# nintendac.net
KiCad netlist of a schematic drawn in EAGLE
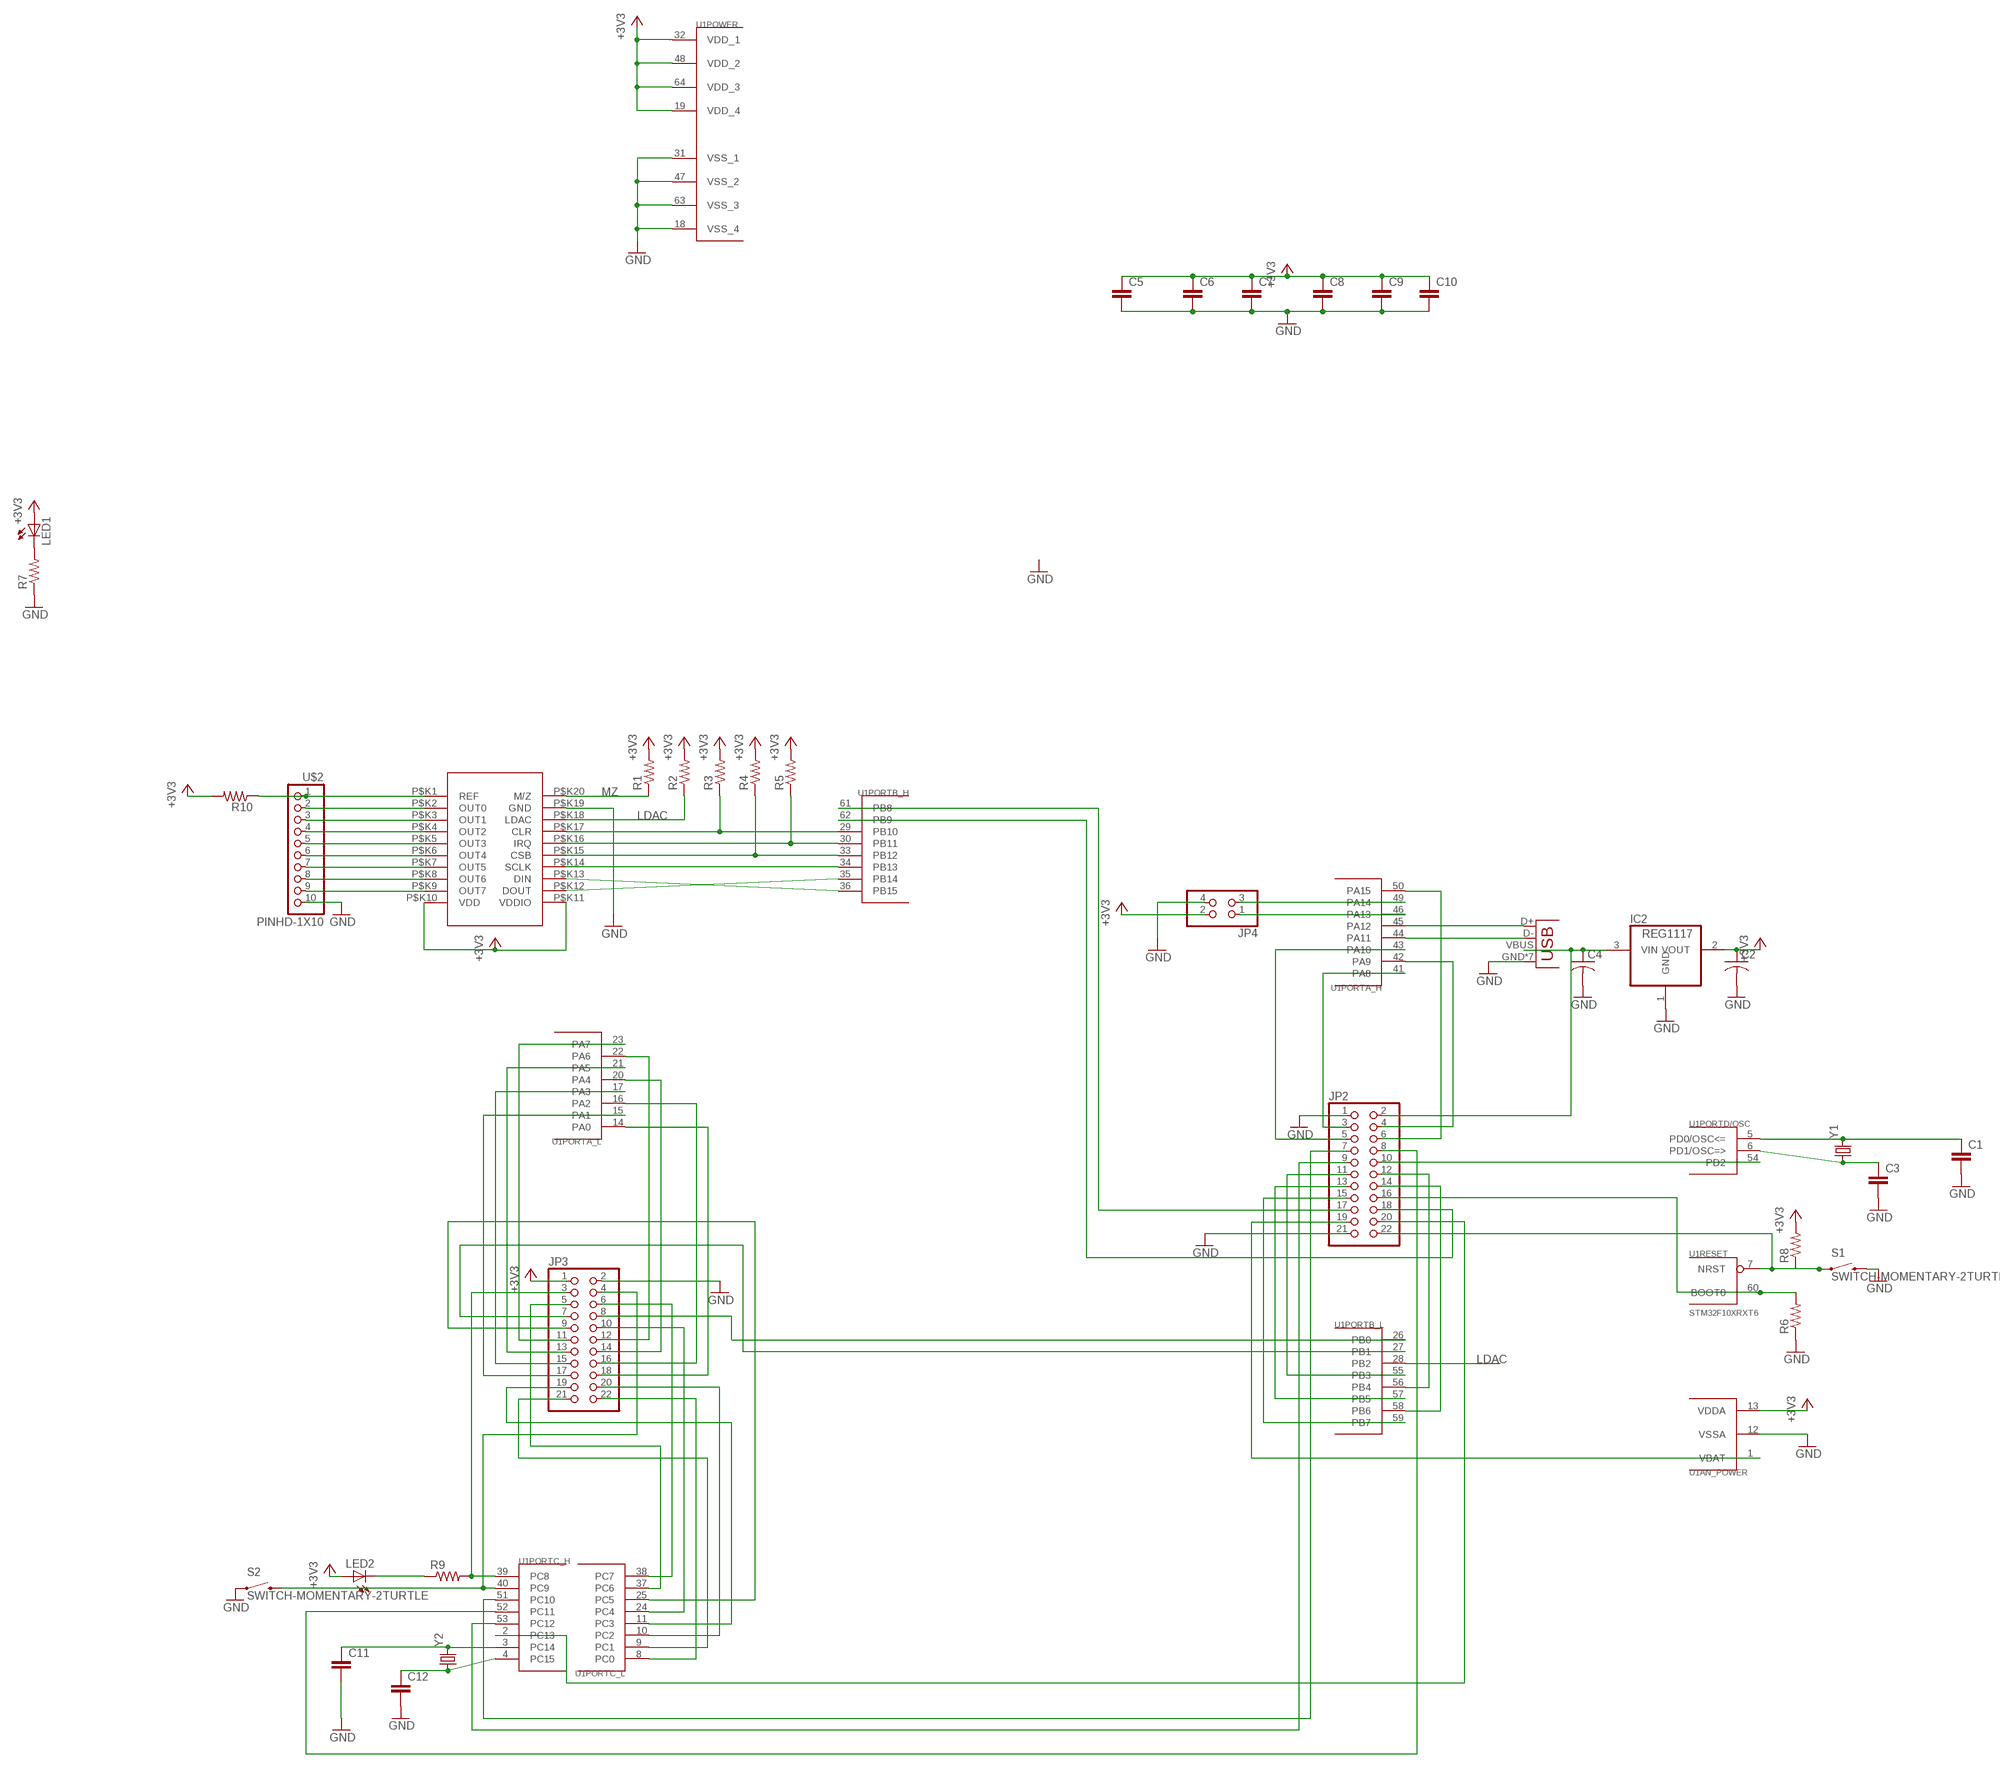
[diagram p0: schematic, sheet 1]

(export (version "E")
  (design (tool "Eeschema 10.0.6"))
  (components
    (comp (ref "C1")
      (value "CAP0805")
      (footprint "eagle-import:0805")
      (libsource (lib "eagle-import") (part "CAP0805"))
    )
    (comp (ref "C2")
      (value "C-USC1210")
      (footprint "eagle-import:C1210")
      (libsource (lib "eagle-import") (part "C-USC1210"))
    )
    (comp (ref "C3")
      (value "CAP0805")
      (footprint "eagle-import:0805")
      (libsource (lib "eagle-import") (part "CAP0805"))
    )
    (comp (ref "C4")
      (value "C-USC1210")
      (footprint "eagle-import:C1210")
      (libsource (lib "eagle-import") (part "C-USC1210"))
    )
    (comp (ref "C5")
      (value "CAP0805")
      (footprint "eagle-import:0805")
      (libsource (lib "eagle-import") (part "CAP0805"))
    )
    (comp (ref "C6")
      (value "CAP0805")
      (footprint "eagle-import:0805")
      (libsource (lib "eagle-import") (part "CAP0805"))
    )
    (comp (ref "C7")
      (value "CAP0805")
      (footprint "eagle-import:0805")
      (libsource (lib "eagle-import") (part "CAP0805"))
    )
    (comp (ref "C8")
      (value "CAP0805")
      (footprint "eagle-import:0805")
      (libsource (lib "eagle-import") (part "CAP0805"))
    )
    (comp (ref "C9")
      (value "CAP0805")
      (footprint "eagle-import:0805")
      (libsource (lib "eagle-import") (part "CAP0805"))
    )
    (comp (ref "C10")
      (value "CAP0805")
      (footprint "eagle-import:0805")
      (libsource (lib "eagle-import") (part "CAP0805"))
    )
    (comp (ref "C11")
      (value "CAP0805")
      (footprint "eagle-import:0805")
      (libsource (lib "eagle-import") (part "CAP0805"))
    )
    (comp (ref "C12")
      (value "CAP0805")
      (footprint "eagle-import:0805")
      (libsource (lib "eagle-import") (part "CAP0805"))
    )
    (comp (ref "IC2")
      (value "REG1117")
      (footprint "eagle-import:SOT223")
      (libsource (lib "eagle-import") (part "REG1117"))
    )
    (comp (ref "JP2")
      (value "PINHD-2X11")
      (footprint "eagle-import:2X11")
      (libsource (lib "eagle-import") (part "PINHD-2X11"))
    )
    (comp (ref "JP3")
      (value "PINHD-2X11")
      (footprint "eagle-import:2X11")
      (libsource (lib "eagle-import") (part "PINHD-2X11"))
    )
    (comp (ref "JP4")
      (value "PINHD-2X2")
      (footprint "eagle-import:2X02")
      (libsource (lib "eagle-import") (part "PINHD-2X2"))
    )
    (comp (ref "LED1")
      (value "LEDCHIP-LED0805")
      (footprint "eagle-import:CHIP-LED0805")
      (libsource (lib "eagle-import") (part "LEDCHIP-LED0805"))
    )
    (comp (ref "LED2")
      (value "LEDCHIP-LED0805")
      (footprint "eagle-import:CHIP-LED0805")
      (libsource (lib "eagle-import") (part "LEDCHIP-LED0805"))
    )
    (comp (ref "R1")
      (value "RESISTOR0805-RES")
      (footprint "eagle-import:0805")
      (libsource (lib "eagle-import") (part "RESISTOR0805-RES"))
    )
    (comp (ref "R2")
      (value "RESISTOR0805-RES")
      (footprint "eagle-import:0805")
      (libsource (lib "eagle-import") (part "RESISTOR0805-RES"))
    )
    (comp (ref "R3")
      (value "RESISTOR0805-RES")
      (footprint "eagle-import:0805")
      (libsource (lib "eagle-import") (part "RESISTOR0805-RES"))
    )
    (comp (ref "R4")
      (value "RESISTOR0805-RES")
      (footprint "eagle-import:0805")
      (libsource (lib "eagle-import") (part "RESISTOR0805-RES"))
    )
    (comp (ref "R5")
      (value "RESISTOR0805-RES")
      (footprint "eagle-import:0805")
      (libsource (lib "eagle-import") (part "RESISTOR0805-RES"))
    )
    (comp (ref "R6")
      (value "RESISTOR0805-RES")
      (footprint "eagle-import:0805")
      (libsource (lib "eagle-import") (part "RESISTOR0805-RES"))
    )
    (comp (ref "R7")
      (value "RESISTOR0805-RES")
      (footprint "eagle-import:0805")
      (libsource (lib "eagle-import") (part "RESISTOR0805-RES"))
    )
    (comp (ref "R8")
      (value "RESISTOR0805-RES")
      (footprint "eagle-import:0805")
      (libsource (lib "eagle-import") (part "RESISTOR0805-RES"))
    )
    (comp (ref "R9")
      (value "RESISTOR0805-RES")
      (footprint "eagle-import:0805")
      (libsource (lib "eagle-import") (part "RESISTOR0805-RES"))
    )
    (comp (ref "R10")
      (value "RESISTOR0805-RES")
      (footprint "eagle-import:0805")
      (libsource (lib "eagle-import") (part "RESISTOR0805-RES"))
    )
    (comp (ref "S1")
      (value "SWITCH-MOMENTARY-2TURTLE")
      (footprint "eagle-import:KMR2")
      (libsource (lib "eagle-import") (part "SWITCH-MOMENTARY-2TURTLE"))
    )
    (comp (ref "S2")
      (value "SWITCH-MOMENTARY-2TURTLE")
      (footprint "eagle-import:KMR2")
      (libsource (lib "eagle-import") (part "SWITCH-MOMENTARY-2TURTLE"))
    )
    (comp (ref "U$1")
      (value "MAX572X")
      (footprint "eagle-import:TSSOP20")
      (libsource (lib "eagle-import") (part "MAX572X"))
    )
    (comp (ref "U$2")
      (value "PINHD-1X10")
      (footprint "eagle-import:1X10-BIG")
      (libsource (lib "eagle-import") (part "PINHD-1X10"))
    )
    (comp (ref "U1")
      (value "STM32F10XRXT6")
      (footprint "eagle-import:TQFP64")
      (libsource (lib "eagle-import") (part "STM32F10XRXT6"))
    )
    (comp (ref "X1")
      (value "USB-MICROB")
      (footprint "eagle-import:USB-MICROB")
      (libsource (lib "eagle-import") (part "USB-MICROB"))
    )
    (comp (ref "Y1")
      (value "CRYSTALHC49US")
      (footprint "eagle-import:HC49US")
      (libsource (lib "eagle-import") (part "CRYSTALHC49US"))
    )
    (comp (ref "Y2")
      (value "CRYSTALTC26H_EZ")
      (footprint "eagle-import:TC26HEZ")
      (libsource (lib "eagle-import") (part "CRYSTALTC26H_EZ"))
    )
  )
  (nets
    (net (code "1") (name "+3V3") (class "Default")
      (node (ref "C10") (pin "1") (pinfunction "1_1") (pintype "passive"))
      (node (ref "C2") (pin "1") (pinfunction "1_1") (pintype "passive"))
      (node (ref "C5") (pin "1") (pinfunction "1_1") (pintype "passive"))
      (node (ref "C6") (pin "1") (pinfunction "1_1") (pintype "passive"))
      (node (ref "C7") (pin "1") (pinfunction "1_1") (pintype "passive"))
      (node (ref "C8") (pin "1") (pinfunction "1_1") (pintype "passive"))
      (node (ref "C9") (pin "1") (pinfunction "1_1") (pintype "passive"))
      (node (ref "IC2") (pin "2") (pinfunction "VOUT_2") (pintype "output"))
      (node (ref "JP3") (pin "1") (pinfunction "1_1") (pintype "passive"))
      (node (ref "JP4") (pin "2") (pinfunction "2_2") (pintype "passive"))
      (node (ref "LED1") (pin "A") (pinfunction "A_A") (pintype "passive"))
      (node (ref "LED2") (pin "A") (pinfunction "A_A") (pintype "passive"))
      (node (ref "R1") (pin "2") (pinfunction "2_2") (pintype "passive"))
      (node (ref "R10") (pin "2") (pinfunction "2_2") (pintype "passive"))
      (node (ref "R2") (pin "2") (pinfunction "2_2") (pintype "passive"))
      (node (ref "R3") (pin "2") (pinfunction "2_2") (pintype "passive"))
      (node (ref "R4") (pin "2") (pinfunction "2_2") (pintype "passive"))
      (node (ref "R5") (pin "2") (pinfunction "2_2") (pintype "passive"))
      (node (ref "R8") (pin "2") (pinfunction "2_2") (pintype "passive"))
      (node (ref "U$1") (pin "P$K10") (pinfunction "VDD_P$K10") (pintype "bidirectional"))
      (node (ref "U$1") (pin "P$K11") (pinfunction "VDDIO_P$K11") (pintype "bidirectional"))
      (node (ref "U1") (pin "13") (pinfunction "VDDA_13") (pintype "power_in"))
      (node (ref "U1") (pin "19") (pinfunction "VDD_4_19") (pintype "power_in"))
      (node (ref "U1") (pin "32") (pinfunction "VDD_1_32") (pintype "power_in"))
      (node (ref "U1") (pin "48") (pinfunction "VDD_2_48") (pintype "power_in"))
      (node (ref "U1") (pin "64") (pinfunction "VDD_3_64") (pintype "power_in"))
    )
    (net (code "2") (name "/LDAC") (class "Default")
      (node (ref "R2") (pin "1") (pinfunction "1_1") (pintype "passive"))
      (node (ref "U$1") (pin "P$K18") (pinfunction "LDAC_P$K18") (pintype "bidirectional"))
      (node (ref "U1") (pin "28") (pinfunction "PB2_28") (pintype "bidirectional"))
    )
    (net (code "3") (name "/MZ") (class "Default")
      (node (ref "R1") (pin "1") (pinfunction "1_1") (pintype "passive"))
      (node (ref "U$1") (pin "P$K20") (pinfunction "M/Z_P$K20") (pintype "bidirectional"))
    )
    (net (code "4") (name "GND") (class "Default")
      (node (ref "C1") (pin "2") (pinfunction "2_2") (pintype "passive"))
      (node (ref "C10") (pin "2") (pinfunction "2_2") (pintype "passive"))
      (node (ref "C11") (pin "2") (pinfunction "2_2") (pintype "passive"))
      (node (ref "C12") (pin "2") (pinfunction "2_2") (pintype "passive"))
      (node (ref "C2") (pin "2") (pinfunction "2_2") (pintype "passive"))
      (node (ref "C3") (pin "2") (pinfunction "2_2") (pintype "passive"))
      (node (ref "C4") (pin "2") (pinfunction "2_2") (pintype "passive"))
      (node (ref "C5") (pin "2") (pinfunction "2_2") (pintype "passive"))
      (node (ref "C6") (pin "2") (pinfunction "2_2") (pintype "passive"))
      (node (ref "C7") (pin "2") (pinfunction "2_2") (pintype "passive"))
      (node (ref "C8") (pin "2") (pinfunction "2_2") (pintype "passive"))
      (node (ref "C9") (pin "2") (pinfunction "2_2") (pintype "passive"))
      (node (ref "IC2") (pin "1") (pinfunction "GND_1") (pintype "power_in"))
      (node (ref "JP2") (pin "1") (pinfunction "1_1") (pintype "passive"))
      (node (ref "JP2") (pin "21") (pinfunction "21_21") (pintype "passive"))
      (node (ref "JP3") (pin "2") (pinfunction "2_2") (pintype "passive"))
      (node (ref "JP4") (pin "4") (pinfunction "4_4") (pintype "passive"))
      (node (ref "R6") (pin "1") (pinfunction "1_1") (pintype "passive"))
      (node (ref "R7") (pin "1") (pinfunction "1_1") (pintype "passive"))
      (node (ref "S1") (pin "3") (pinfunction "2_3") (pintype "passive"))
      (node (ref "S2") (pin "1") (pinfunction "1_1") (pintype "passive"))
      (node (ref "U$1") (pin "P$K19") (pinfunction "GND_P$K19") (pintype "bidirectional"))
      (node (ref "U$2") (pin "10") (pinfunction "10_10") (pintype "passive"))
      (node (ref "U1") (pin "12") (pinfunction "VSSA_12") (pintype "power_in"))
      (node (ref "U1") (pin "18") (pinfunction "VSS_4_18") (pintype "power_in"))
      (node (ref "U1") (pin "31") (pinfunction "VSS_1_31") (pintype "power_in"))
      (node (ref "U1") (pin "47") (pinfunction "VSS_2_47") (pintype "power_in"))
      (node (ref "U1") (pin "63") (pinfunction "VSS_3_63") (pintype "power_in"))
      (node (ref "X1") (pin "GND") (pinfunction "GND_GND") (pintype "bidirectional"))
      (node (ref "X1") (pin "P1") (pinfunction "GND_P1") (pintype "bidirectional"))
      (node (ref "X1") (pin "P2") (pinfunction "GND_P2") (pintype "bidirectional"))
      (node (ref "X1") (pin "P3") (pinfunction "GND_P3") (pintype "bidirectional"))
      (node (ref "X1") (pin "P4") (pinfunction "GND_P4") (pintype "bidirectional"))
      (node (ref "X1") (pin "P5") (pinfunction "GND_P5") (pintype "bidirectional"))
      (node (ref "X1") (pin "P6") (pinfunction "GND_P6") (pintype "bidirectional"))
    )
    (net (code "5") (name "Net-(IC2-VIN)") (class "Default")
      (node (ref "C4") (pin "1") (pinfunction "1_1") (pintype "passive"))
      (node (ref "IC2") (pin "3") (pinfunction "VIN_3") (pintype "input"))
      (node (ref "JP2") (pin "2") (pinfunction "2_2") (pintype "passive"))
      (node (ref "X1") (pin "VBUS") (pinfunction "VBUS_VBUS") (pintype "bidirectional"))
    )
    (net (code "6") (name "Net-(LED1-PadC)") (class "Default")
      (node (ref "LED1") (pin "C") (pinfunction "C_C") (pintype "passive"))
      (node (ref "R7") (pin "2") (pinfunction "2_2") (pintype "passive"))
    )
    (net (code "7") (name "Net-(LED2-PadC)") (class "Default")
      (node (ref "LED2") (pin "C") (pinfunction "C_C") (pintype "passive"))
      (node (ref "R9") (pin "1") (pinfunction "1_1") (pintype "passive"))
    )
    (net (code "8") (name "Net-(S2-2)") (class "Default")
      (node (ref "JP3") (pin "4") (pinfunction "4_4") (pintype "passive"))
      (node (ref "S2") (pin "3") (pinfunction "2_3") (pintype "passive"))
      (node (ref "U1") (pin "40") (pinfunction "PC9_40") (pintype "bidirectional"))
    )
    (net (code "9") (name "Net-(U$1-CLR)") (class "Default")
      (node (ref "R3") (pin "1") (pinfunction "1_1") (pintype "passive"))
      (node (ref "U$1") (pin "P$K17") (pinfunction "CLR_P$K17") (pintype "bidirectional"))
      (node (ref "U1") (pin "29") (pinfunction "PB10_29") (pintype "bidirectional"))
    )
    (net (code "10") (name "Net-(U$1-CSB)") (class "Default")
      (node (ref "R4") (pin "1") (pinfunction "1_1") (pintype "passive"))
      (node (ref "U$1") (pin "P$K15") (pinfunction "CSB_P$K15") (pintype "bidirectional"))
      (node (ref "U1") (pin "33") (pinfunction "PB12_33") (pintype "bidirectional"))
    )
    (net (code "11") (name "Net-(U$1-DIN)") (class "Default")
      (node (ref "U$1") (pin "P$K13") (pinfunction "DIN_P$K13") (pintype "bidirectional"))
      (node (ref "U1") (pin "36") (pinfunction "PB15_36") (pintype "bidirectional"))
    )
    (net (code "12") (name "Net-(U$1-DOUT)") (class "Default")
      (node (ref "U$1") (pin "P$K12") (pinfunction "DOUT_P$K12") (pintype "bidirectional"))
      (node (ref "U1") (pin "35") (pinfunction "PB14_35") (pintype "bidirectional"))
    )
    (net (code "13") (name "Net-(U$1-IRQ)") (class "Default")
      (node (ref "R5") (pin "1") (pinfunction "1_1") (pintype "passive"))
      (node (ref "U$1") (pin "P$K16") (pinfunction "IRQ_P$K16") (pintype "bidirectional"))
      (node (ref "U1") (pin "30") (pinfunction "PB11_30") (pintype "bidirectional"))
    )
    (net (code "14") (name "Net-(U$1-OUT0)") (class "Default")
      (node (ref "U$1") (pin "P$K2") (pinfunction "OUT0_P$K2") (pintype "bidirectional"))
      (node (ref "U$2") (pin "2") (pinfunction "2_2") (pintype "passive"))
    )
    (net (code "15") (name "Net-(U$1-OUT1)") (class "Default")
      (node (ref "U$1") (pin "P$K3") (pinfunction "OUT1_P$K3") (pintype "bidirectional"))
      (node (ref "U$2") (pin "3") (pinfunction "3_3") (pintype "passive"))
    )
    (net (code "16") (name "Net-(U$1-OUT2)") (class "Default")
      (node (ref "U$1") (pin "P$K4") (pinfunction "OUT2_P$K4") (pintype "bidirectional"))
      (node (ref "U$2") (pin "4") (pinfunction "4_4") (pintype "passive"))
    )
    (net (code "17") (name "Net-(U$1-OUT3)") (class "Default")
      (node (ref "U$1") (pin "P$K5") (pinfunction "OUT3_P$K5") (pintype "bidirectional"))
      (node (ref "U$2") (pin "5") (pinfunction "5_5") (pintype "passive"))
    )
    (net (code "18") (name "Net-(U$1-OUT4)") (class "Default")
      (node (ref "U$1") (pin "P$K6") (pinfunction "OUT4_P$K6") (pintype "bidirectional"))
      (node (ref "U$2") (pin "6") (pinfunction "6_6") (pintype "passive"))
    )
    (net (code "19") (name "Net-(U$1-OUT5)") (class "Default")
      (node (ref "U$1") (pin "P$K7") (pinfunction "OUT5_P$K7") (pintype "bidirectional"))
      (node (ref "U$2") (pin "7") (pinfunction "7_7") (pintype "passive"))
    )
    (net (code "20") (name "Net-(U$1-OUT6)") (class "Default")
      (node (ref "U$1") (pin "P$K8") (pinfunction "OUT6_P$K8") (pintype "bidirectional"))
      (node (ref "U$2") (pin "8") (pinfunction "8_8") (pintype "passive"))
    )
    (net (code "21") (name "Net-(U$1-OUT7)") (class "Default")
      (node (ref "U$1") (pin "P$K9") (pinfunction "OUT7_P$K9") (pintype "bidirectional"))
      (node (ref "U$2") (pin "9") (pinfunction "9_9") (pintype "passive"))
    )
    (net (code "22") (name "Net-(U$1-REF)") (class "Default")
      (node (ref "R10") (pin "1") (pinfunction "1_1") (pintype "passive"))
      (node (ref "U$1") (pin "P$K1") (pinfunction "REF_P$K1") (pintype "bidirectional"))
      (node (ref "U$2") (pin "1") (pinfunction "1_1") (pintype "passive"))
    )
    (net (code "23") (name "Net-(U$1-SCLK)") (class "Default")
      (node (ref "U$1") (pin "P$K14") (pinfunction "SCLK_P$K14") (pintype "bidirectional"))
      (node (ref "U1") (pin "34") (pinfunction "PB13_34") (pintype "bidirectional"))
    )
    (net (code "24") (name "Net-(U1A-VBAT)") (class "Default")
      (node (ref "JP2") (pin "19") (pinfunction "19_19") (pintype "passive"))
      (node (ref "U1") (pin "1") (pinfunction "VBAT_1") (pintype "power_in"))
    )
    (net (code "25") (name "Net-(U1B-PA8)") (class "Default")
      (node (ref "JP2") (pin "3") (pinfunction "3_3") (pintype "passive"))
      (node (ref "U1") (pin "41") (pinfunction "PA8_41") (pintype "bidirectional"))
    )
    (net (code "26") (name "Net-(U1B-PA9)") (class "Default")
      (node (ref "JP2") (pin "4") (pinfunction "4_4") (pintype "passive"))
      (node (ref "U1") (pin "42") (pinfunction "PA9_42") (pintype "bidirectional"))
    )
    (net (code "27") (name "Net-(U1B-PA10)") (class "Default")
      (node (ref "JP2") (pin "5") (pinfunction "5_5") (pintype "passive"))
      (node (ref "U1") (pin "43") (pinfunction "PA10_43") (pintype "bidirectional"))
    )
    (net (code "28") (name "Net-(U1B-PA11)") (class "Default")
      (node (ref "U1") (pin "44") (pinfunction "PA11_44") (pintype "bidirectional"))
      (node (ref "X1") (pin "D-") (pinfunction "D-_D-") (pintype "bidirectional"))
    )
    (net (code "29") (name "Net-(U1B-PA12)") (class "Default")
      (node (ref "U1") (pin "45") (pinfunction "PA12_45") (pintype "bidirectional"))
      (node (ref "X1") (pin "D+") (pinfunction "D+_D+") (pintype "bidirectional"))
    )
    (net (code "30") (name "Net-(U1B-PA13)") (class "Default")
      (node (ref "JP4") (pin "1") (pinfunction "1_1") (pintype "passive"))
      (node (ref "U1") (pin "46") (pinfunction "PA13_46") (pintype "bidirectional"))
    )
    (net (code "31") (name "Net-(U1B-PA14)") (class "Default")
      (node (ref "JP4") (pin "3") (pinfunction "3_3") (pintype "passive"))
      (node (ref "U1") (pin "49") (pinfunction "PA14_49") (pintype "bidirectional"))
    )
    (net (code "32") (name "Net-(U1B-PA15)") (class "Default")
      (node (ref "JP2") (pin "6") (pinfunction "6_6") (pintype "passive"))
      (node (ref "U1") (pin "50") (pinfunction "PA15_50") (pintype "bidirectional"))
    )
    (net (code "33") (name "Net-(U1C-PA0)") (class "Default")
      (node (ref "JP3") (pin "18") (pinfunction "18_18") (pintype "passive"))
      (node (ref "U1") (pin "14") (pinfunction "PA0_14") (pintype "bidirectional"))
    )
    (net (code "34") (name "Net-(U1C-PA1)") (class "Default")
      (node (ref "JP3") (pin "17") (pinfunction "17_17") (pintype "passive"))
      (node (ref "U1") (pin "15") (pinfunction "PA1_15") (pintype "bidirectional"))
    )
    (net (code "35") (name "Net-(U1C-PA2)") (class "Default")
      (node (ref "JP3") (pin "16") (pinfunction "16_16") (pintype "passive"))
      (node (ref "U1") (pin "16") (pinfunction "PA2_16") (pintype "bidirectional"))
    )
    (net (code "36") (name "Net-(U1C-PA3)") (class "Default")
      (node (ref "JP3") (pin "15") (pinfunction "15_15") (pintype "passive"))
      (node (ref "U1") (pin "17") (pinfunction "PA3_17") (pintype "bidirectional"))
    )
    (net (code "37") (name "Net-(U1C-PA4)") (class "Default")
      (node (ref "JP3") (pin "14") (pinfunction "14_14") (pintype "passive"))
      (node (ref "U1") (pin "20") (pinfunction "PA4_20") (pintype "bidirectional"))
    )
    (net (code "38") (name "Net-(U1C-PA5)") (class "Default")
      (node (ref "JP3") (pin "13") (pinfunction "13_13") (pintype "passive"))
      (node (ref "U1") (pin "21") (pinfunction "PA5_21") (pintype "bidirectional"))
    )
    (net (code "39") (name "Net-(U1C-PA6)") (class "Default")
      (node (ref "JP3") (pin "12") (pinfunction "12_12") (pintype "passive"))
      (node (ref "U1") (pin "22") (pinfunction "PA6_22") (pintype "bidirectional"))
    )
    (net (code "40") (name "Net-(U1C-PA7)") (class "Default")
      (node (ref "JP3") (pin "11") (pinfunction "11_11") (pintype "passive"))
      (node (ref "U1") (pin "23") (pinfunction "PA7_23") (pintype "bidirectional"))
    )
    (net (code "41") (name "Net-(U1D-PB8)") (class "Default")
      (node (ref "JP2") (pin "17") (pinfunction "17_17") (pintype "passive"))
      (node (ref "U1") (pin "61") (pinfunction "PB8_61") (pintype "bidirectional"))
    )
    (net (code "42") (name "Net-(U1D-PB9)") (class "Default")
      (node (ref "JP2") (pin "18") (pinfunction "18_18") (pintype "passive"))
      (node (ref "U1") (pin "62") (pinfunction "PB9_62") (pintype "bidirectional"))
    )
    (net (code "43") (name "Net-(U1E-PB0)") (class "Default")
      (node (ref "JP3") (pin "8") (pinfunction "8_8") (pintype "passive"))
      (node (ref "U1") (pin "26") (pinfunction "PB0_26") (pintype "bidirectional"))
    )
    (net (code "44") (name "Net-(U1E-PB1)") (class "Default")
      (node (ref "JP3") (pin "7") (pinfunction "7_7") (pintype "passive"))
      (node (ref "U1") (pin "27") (pinfunction "PB1_27") (pintype "bidirectional"))
    )
    (net (code "45") (name "Net-(U1E-PB3)") (class "Default")
      (node (ref "JP2") (pin "11") (pinfunction "11_11") (pintype "passive"))
      (node (ref "U1") (pin "55") (pinfunction "PB3_55") (pintype "bidirectional"))
    )
    (net (code "46") (name "Net-(U1E-PB4)") (class "Default")
      (node (ref "JP2") (pin "12") (pinfunction "12_12") (pintype "passive"))
      (node (ref "U1") (pin "56") (pinfunction "PB4_56") (pintype "bidirectional"))
    )
    (net (code "47") (name "Net-(U1E-PB5)") (class "Default")
      (node (ref "JP2") (pin "13") (pinfunction "13_13") (pintype "passive"))
      (node (ref "U1") (pin "57") (pinfunction "PB5_57") (pintype "bidirectional"))
    )
    (net (code "48") (name "Net-(U1E-PB6)") (class "Default")
      (node (ref "JP2") (pin "14") (pinfunction "14_14") (pintype "passive"))
      (node (ref "U1") (pin "58") (pinfunction "PB6_58") (pintype "bidirectional"))
    )
    (net (code "49") (name "Net-(U1E-PB7)") (class "Default")
      (node (ref "JP2") (pin "15") (pinfunction "15_15") (pintype "passive"))
      (node (ref "U1") (pin "59") (pinfunction "PB7_59") (pintype "bidirectional"))
    )
    (net (code "50") (name "Net-(U1F-PC8)") (class "Default")
      (node (ref "JP3") (pin "3") (pinfunction "3_3") (pintype "passive"))
      (node (ref "R9") (pin "2") (pinfunction "2_2") (pintype "passive"))
      (node (ref "U1") (pin "39") (pinfunction "PC8_39") (pintype "bidirectional"))
    )
    (net (code "51") (name "Net-(U1F-PC10)") (class "Default")
      (node (ref "JP2") (pin "7") (pinfunction "7_7") (pintype "passive"))
      (node (ref "U1") (pin "51") (pinfunction "PC10_51") (pintype "bidirectional"))
    )
    (net (code "52") (name "Net-(U1F-PC11)") (class "Default")
      (node (ref "JP2") (pin "8") (pinfunction "8_8") (pintype "passive"))
      (node (ref "U1") (pin "52") (pinfunction "PC11_52") (pintype "bidirectional"))
    )
    (net (code "53") (name "Net-(U1F-PC12)") (class "Default")
      (node (ref "JP2") (pin "9") (pinfunction "9_9") (pintype "passive"))
      (node (ref "U1") (pin "53") (pinfunction "PC12_53") (pintype "bidirectional"))
    )
    (net (code "54") (name "Net-(U1F-PC13)") (class "Default")
      (node (ref "JP2") (pin "20") (pinfunction "20_20") (pintype "passive"))
      (node (ref "U1") (pin "2") (pinfunction "PC13_2") (pintype "bidirectional"))
    )
    (net (code "55") (name "Net-(U1F-PC14)") (class "Default")
      (node (ref "C11") (pin "1") (pinfunction "1_1") (pintype "passive"))
      (node (ref "U1") (pin "3") (pinfunction "PC14_3") (pintype "bidirectional"))
      (node (ref "Y2") (pin "2") (pinfunction "2_2") (pintype "passive"))
    )
    (net (code "56") (name "Net-(U1F-PC15)") (class "Default")
      (node (ref "C12") (pin "1") (pinfunction "1_1") (pintype "passive"))
      (node (ref "U1") (pin "4") (pinfunction "PC15_4") (pintype "bidirectional"))
      (node (ref "Y2") (pin "1") (pinfunction "1_1") (pintype "passive"))
    )
    (net (code "57") (name "Net-(U1G-PC0)") (class "Default")
      (node (ref "JP3") (pin "22") (pinfunction "22_22") (pintype "passive"))
      (node (ref "U1") (pin "8") (pinfunction "PC0_8") (pintype "bidirectional"))
    )
    (net (code "58") (name "Net-(U1G-PC1)") (class "Default")
      (node (ref "JP3") (pin "21") (pinfunction "21_21") (pintype "passive"))
      (node (ref "U1") (pin "9") (pinfunction "PC1_9") (pintype "bidirectional"))
    )
    (net (code "59") (name "Net-(U1G-PC2)") (class "Default")
      (node (ref "JP3") (pin "20") (pinfunction "20_20") (pintype "passive"))
      (node (ref "U1") (pin "10") (pinfunction "PC2_10") (pintype "bidirectional"))
    )
    (net (code "60") (name "Net-(U1G-PC3)") (class "Default")
      (node (ref "JP3") (pin "19") (pinfunction "19_19") (pintype "passive"))
      (node (ref "U1") (pin "11") (pinfunction "PC3_11") (pintype "bidirectional"))
    )
    (net (code "61") (name "Net-(U1G-PC4)") (class "Default")
      (node (ref "JP3") (pin "10") (pinfunction "10_10") (pintype "passive"))
      (node (ref "U1") (pin "24") (pinfunction "PC4_24") (pintype "bidirectional"))
    )
    (net (code "62") (name "Net-(U1G-PC5)") (class "Default")
      (node (ref "JP3") (pin "9") (pinfunction "9_9") (pintype "passive"))
      (node (ref "U1") (pin "25") (pinfunction "PC5_25") (pintype "bidirectional"))
    )
    (net (code "63") (name "Net-(U1G-PC6)") (class "Default")
      (node (ref "JP3") (pin "5") (pinfunction "5_5") (pintype "passive"))
      (node (ref "U1") (pin "37") (pinfunction "PC6_37") (pintype "bidirectional"))
    )
    (net (code "64") (name "Net-(U1G-PC7)") (class "Default")
      (node (ref "JP3") (pin "6") (pinfunction "6_6") (pintype "passive"))
      (node (ref "U1") (pin "38") (pinfunction "PC7_38") (pintype "bidirectional"))
    )
    (net (code "65") (name "Net-(U1H-PD0{slash}OSC<=)") (class "Default")
      (node (ref "C1") (pin "1") (pinfunction "1_1") (pintype "passive"))
      (node (ref "U1") (pin "5") (pinfunction "PD0/OSC<=_5") (pintype "bidirectional"))
      (node (ref "Y1") (pin "2") (pinfunction "2_2") (pintype "passive"))
    )
    (net (code "66") (name "Net-(U1H-PD1{slash}OSC=>)") (class "Default")
      (node (ref "C3") (pin "1") (pinfunction "1_1") (pintype "passive"))
      (node (ref "U1") (pin "6") (pinfunction "PD1/OSC=>_6") (pintype "bidirectional"))
      (node (ref "Y1") (pin "1") (pinfunction "1_1") (pintype "passive"))
    )
    (net (code "67") (name "Net-(U1H-PD2)") (class "Default")
      (node (ref "JP2") (pin "10") (pinfunction "10_10") (pintype "passive"))
      (node (ref "U1") (pin "54") (pinfunction "PD2_54") (pintype "bidirectional"))
    )
    (net (code "68") (name "Net-(U1J-BOOT0)") (class "Default")
      (node (ref "JP2") (pin "16") (pinfunction "16_16") (pintype "passive"))
      (node (ref "R6") (pin "2") (pinfunction "2_2") (pintype "passive"))
      (node (ref "U1") (pin "60") (pinfunction "BOOT0_60") (pintype "input"))
    )
    (net (code "69") (name "Net-(U1J-NRST)") (class "Default")
      (node (ref "JP2") (pin "22") (pinfunction "22_22") (pintype "passive"))
      (node (ref "R8") (pin "1") (pinfunction "1_1") (pintype "passive"))
      (node (ref "S1") (pin "1") (pinfunction "1_1") (pintype "passive"))
      (node (ref "U1") (pin "7") (pinfunction "NRST_7") (pintype "input"))
    )
  )
)
